# PORT_EX.net
KiCad netlist of a schematic drawn in Altium Designer
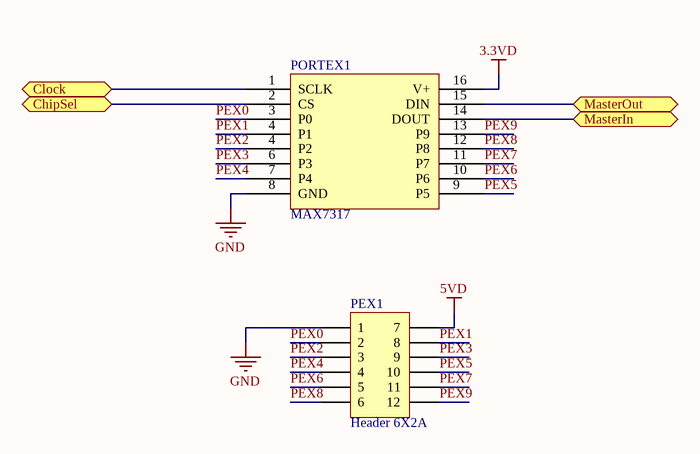
[diagram p0: PORT_EX.SchDoc]

(export (version "E")
  (design (tool "Eeschema 10.0.6"))
  (components
    (comp (ref "PEX1")
      (value "Header 6X2A")
      (footprint "HDR2X6_CEN")
      (description "Header, 6-Pin, Dual row")
      (fields (field (name "PUBLISHER") "Altium Limited"))
      (libsource (lib "Miscellaneous Connectors") (part "Header 6X2A"))
    )
    (comp (ref "PORTEX1")
      (value "MAX7317")
      (footprint "MAX7317")
      (libsource (lib "Crystal") (part "MAX7317"))
    )
  )
  (nets
    (net (code "1") (name "/ChipSel") (class "Default")
      (node (ref "PORTEX1") (pin "2") (pinfunction "CS_2") (pintype "passive"))
    )
    (net (code "2") (name "/Clock") (class "Default")
      (node (ref "PORTEX1") (pin "1") (pinfunction "SCLK_1") (pintype "passive"))
    )
    (net (code "3") (name "/MasterIn") (class "Default")
      (node (ref "PORTEX1") (pin "14") (pinfunction "DOUT_14") (pintype "passive"))
    )
    (net (code "4") (name "/MasterOut") (class "Default")
      (node (ref "PORTEX1") (pin "15") (pinfunction "DIN_15") (pintype "passive"))
    )
    (net (code "5") (name "/PEX0") (class "Default")
      (node (ref "PEX1") (pin "2") (pinfunction "2_2") (pintype "passive"))
      (node (ref "PORTEX1") (pin "3") (pinfunction "P0_3") (pintype "passive"))
    )
    (net (code "6") (name "/PEX1") (class "Default")
      (node (ref "PEX1") (pin "8") (pinfunction "8_8") (pintype "passive"))
      (node (ref "PORTEX1") (pin "4") (pinfunction "P1_4") (pintype "passive"))
    )
    (net (code "7") (name "/PEX2") (class "Default")
      (node (ref "PEX1") (pin "3") (pinfunction "3_3") (pintype "passive"))
      (node (ref "PORTEX1") (pin "4") (pinfunction "P2_4") (pintype "passive"))
    )
    (net (code "8") (name "/PEX3") (class "Default")
      (node (ref "PEX1") (pin "9") (pinfunction "9_9") (pintype "passive"))
      (node (ref "PORTEX1") (pin "6") (pinfunction "P3_6") (pintype "passive"))
    )
    (net (code "9") (name "/PEX4") (class "Default")
      (node (ref "PEX1") (pin "4") (pinfunction "4_4") (pintype "passive"))
      (node (ref "PORTEX1") (pin "7") (pinfunction "P4_7") (pintype "passive"))
    )
    (net (code "10") (name "/PEX5") (class "Default")
      (node (ref "PEX1") (pin "10") (pinfunction "10_10") (pintype "passive"))
      (node (ref "PORTEX1") (pin "9") (pinfunction "P5_9") (pintype "passive"))
    )
    (net (code "11") (name "/PEX6") (class "Default")
      (node (ref "PEX1") (pin "5") (pinfunction "5_5") (pintype "passive"))
      (node (ref "PORTEX1") (pin "10") (pinfunction "P6_10") (pintype "passive"))
    )
    (net (code "12") (name "/PEX7") (class "Default")
      (node (ref "PEX1") (pin "11") (pinfunction "11_11") (pintype "passive"))
      (node (ref "PORTEX1") (pin "11") (pinfunction "P7_11") (pintype "passive"))
    )
    (net (code "13") (name "/PEX8") (class "Default")
      (node (ref "PEX1") (pin "6") (pinfunction "6_6") (pintype "passive"))
      (node (ref "PORTEX1") (pin "12") (pinfunction "P8_12") (pintype "passive"))
    )
    (net (code "14") (name "/PEX9") (class "Default")
      (node (ref "PEX1") (pin "12") (pinfunction "12_12") (pintype "passive"))
      (node (ref "PORTEX1") (pin "13") (pinfunction "P9_13") (pintype "passive"))
    )
    (net (code "15") (name "3.3VD") (class "Default")
      (node (ref "PORTEX1") (pin "16") (pinfunction "V+_16") (pintype "passive"))
    )
    (net (code "16") (name "5VD") (class "Default")
      (node (ref "PEX1") (pin "7") (pinfunction "7_7") (pintype "passive"))
    )
    (net (code "17") (name "GND") (class "Default")
      (node (ref "PEX1") (pin "1") (pinfunction "1_1") (pintype "passive"))
      (node (ref "PORTEX1") (pin "8") (pinfunction "GND_8") (pintype "passive"))
    )
  )
)
